# Buck_converter.net
KiCad netlist of a schematic drawn in Altium Designer
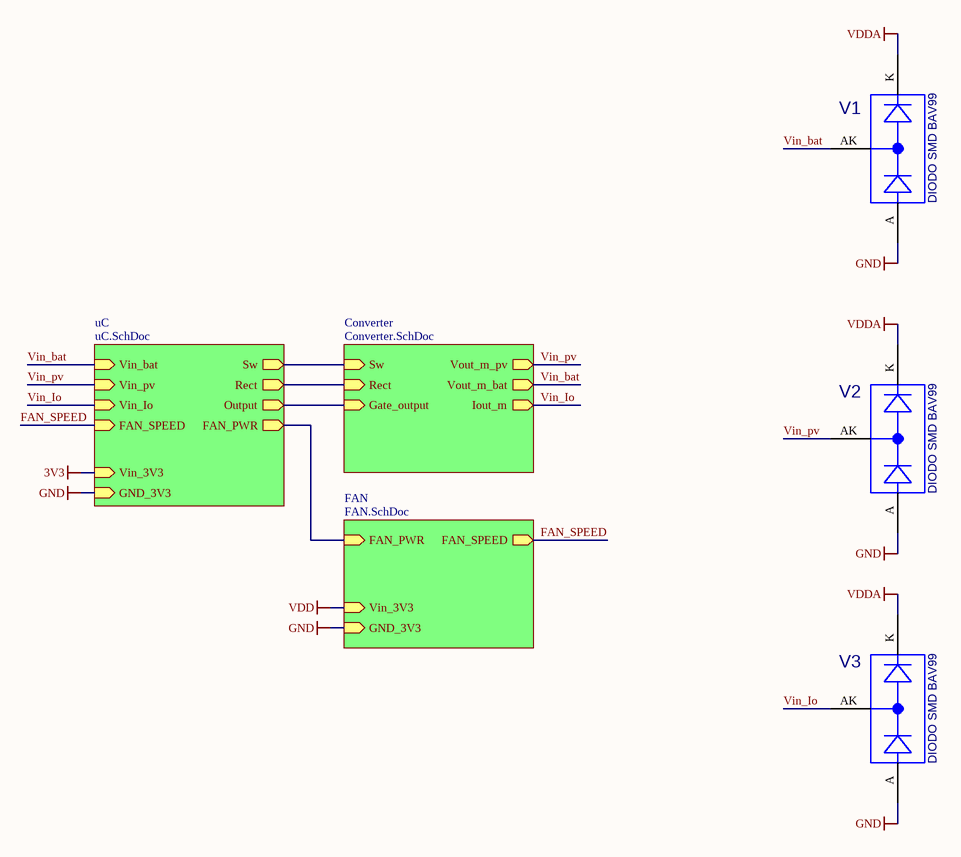
[diagram p0: Buck_converter.SchDoc]

(export (version "E")
  (design (tool "Eeschema 10.0.6"))
  (components
    (comp (ref "V1")
      (value "DIODO SMD BAV99")
      (footprint "SOT23-BAV99A")
      (fields (field (name "Comment") "10574587"))
      (libsource (lib "Buck_Converter") (part "DIODO BAS40"))
    )
    (comp (ref "V2")
      (value "DIODO SMD BAV99")
      (footprint "SOT23-BAV99A")
      (fields (field (name "Comment") "10574587"))
      (libsource (lib "Buck_Converter") (part "DIODO BAS40"))
    )
    (comp (ref "V3")
      (value "DIODO SMD BAV99")
      (footprint "SOT23-BAV99A")
      (fields (field (name "Comment") "10574587"))
      (libsource (lib "Buck_Converter") (part "DIODO BAS40"))
    )
  )
  (nets
    (net (code "6") (name "/Vin_Io") (class "Default")
      (node (ref "V3") (pin "AK") (pinfunction "AK_AK") (pintype "passive"))
    )
    (net (code "7") (name "/Vin_bat") (class "Default")
      (node (ref "V1") (pin "AK") (pinfunction "AK_AK") (pintype "passive"))
    )
    (net (code "8") (name "/Vin_pv") (class "Default")
      (node (ref "V2") (pin "AK") (pinfunction "AK_AK") (pintype "passive"))
    )
    (net (code "10") (name "GND") (class "Default")
      (node (ref "V1") (pin "A") (pinfunction "A_A") (pintype "passive"))
      (node (ref "V2") (pin "A") (pinfunction "A_A") (pintype "passive"))
      (node (ref "V3") (pin "A") (pinfunction "A_A") (pintype "passive"))
    )
    (net (code "12") (name "VDDA") (class "Default")
      (node (ref "V1") (pin "K") (pinfunction "K_K") (pintype "passive"))
      (node (ref "V2") (pin "K") (pinfunction "K_K") (pintype "passive"))
      (node (ref "V3") (pin "K") (pinfunction "K_K") (pintype "passive"))
    )
  )
)
